# bits.net
KiCad netlist of a schematic drawn in EAGLE
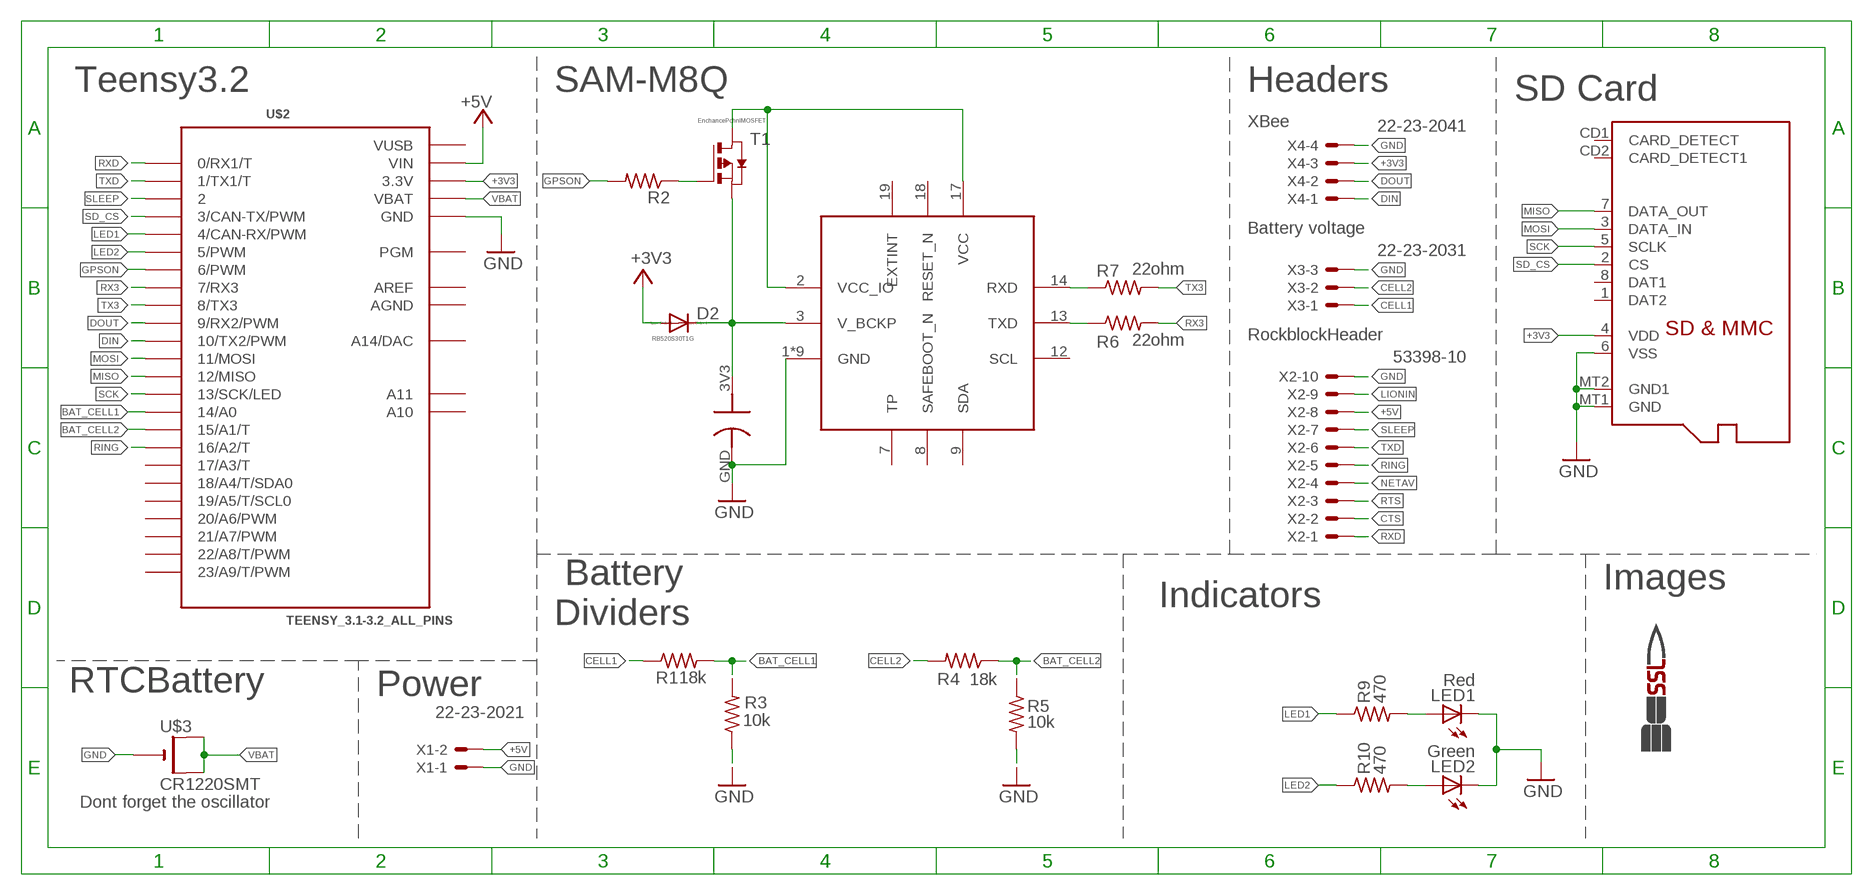
[diagram p0: schematic, sheet 1]

(export (version "E")
  (design (tool "Eeschema 10.0.6"))
  (components
    (comp (ref "C1")
      (value "0.2F elna supercap")
      (footprint "eagle-import:ELNASUPERCAP")
      (libsource (lib "eagle-import") (part "DCK-3RE204T614-ES"))
    )
    (comp (ref "D2")
      (value "RB520S30T1G")
      (footprint "eagle-import:SOD523")
      (libsource (lib "eagle-import") (part "DIODE-SOD523"))
    )
    (comp (ref "IC1")
      (value "SAM-M8Q")
      (footprint "eagle-import:SAM-M8Q")
      (libsource (lib "eagle-import") (part "SAM-M8Q"))
    )
    (comp (ref "IMAG1")
      (value "SSL.3IN_SILK")
      (footprint "eagle-import:SSL_SILK_.3IN")
      (libsource (lib "eagle-import") (part "SSL.3IN_SILK"))
    )
    (comp (ref "LED1")
      (value "Red")
      (footprint "eagle-import:CHIP-LED0603")
      (libsource (lib "eagle-import") (part "LEDCHIP-LED0603"))
    )
    (comp (ref "LED2")
      (value "Green")
      (footprint "eagle-import:CHIP-LED0603")
      (libsource (lib "eagle-import") (part "LEDCHIP-LED0603"))
    )
    (comp (ref "R1")
      (value "18k")
      (footprint "eagle-import:R0603")
      (libsource (lib "eagle-import") (part "R-US_R0603"))
    )
    (comp (ref "R2")
      (value "R-US_R0603")
      (footprint "eagle-import:R0603")
      (libsource (lib "eagle-import") (part "R-US_R0603"))
    )
    (comp (ref "R3")
      (value "10k")
      (footprint "eagle-import:R0603")
      (libsource (lib "eagle-import") (part "R-US_R0603"))
    )
    (comp (ref "R4")
      (value "18k")
      (footprint "eagle-import:R0603")
      (libsource (lib "eagle-import") (part "R-US_R0603"))
    )
    (comp (ref "R5")
      (value "10k")
      (footprint "eagle-import:R0603")
      (libsource (lib "eagle-import") (part "R-US_R0603"))
    )
    (comp (ref "R6")
      (value "22ohm")
      (footprint "eagle-import:R0603")
      (libsource (lib "eagle-import") (part "R-US_R0603"))
    )
    (comp (ref "R7")
      (value "22ohm")
      (footprint "eagle-import:R0603")
      (libsource (lib "eagle-import") (part "R-US_R0603"))
    )
    (comp (ref "R9")
      (value "470")
      (footprint "eagle-import:R0603")
      (libsource (lib "eagle-import") (part "R-US_R0603"))
    )
    (comp (ref "R10")
      (value "470")
      (footprint "eagle-import:R0603")
      (libsource (lib "eagle-import") (part "R-US_R0603"))
    )
    (comp (ref "T1")
      (value "EnchancePchnlMOSFET")
      (footprint "eagle-import:SOT-23")
      (libsource (lib "eagle-import") (part "PMOSSOT23"))
    )
    (comp (ref "U$1")
      (value "MICROSD")
      (footprint "eagle-import:MICROSD")
      (libsource (lib "eagle-import") (part "MICROSD"))
    )
    (comp (ref "U$2")
      (value "TEENSY_3.1-3.2_ALL_PINS")
      (footprint "eagle-import:TEENSY_3.0-3.2&LC_ALL_PINS")
      (libsource (lib "eagle-import") (part "TEENSY_3.1-3.2_ALL_PINS"))
    )
    (comp (ref "U$3")
      (value "CR1220SMT")
      (footprint "eagle-import:CR1220-SMD")
      (libsource (lib "eagle-import") (part "CR1220SMT"))
    )
    (comp (ref "X1")
      (value "22-23-2021")
      (footprint "eagle-import:22-23-2021")
      (fields (field (name "MF") "MOLEX"))
      (libsource (lib "eagle-import") (part "22-23-2021"))
    )
    (comp (ref "X2")
      (value "53398-10")
      (footprint "eagle-import:53398-10")
      (fields (field (name "MF") "MOLEX") (field (name "MPN") "53398-1071"))
      (libsource (lib "eagle-import") (part "53?-10398"))
    )
    (comp (ref "X3")
      (value "22-23-2031")
      (footprint "eagle-import:22-23-2031")
      (fields (field (name "MF") "MOLEX"))
      (libsource (lib "eagle-import") (part "22-23-2031"))
    )
    (comp (ref "X4")
      (value "22-23-2041")
      (footprint "eagle-import:22-23-2041")
      (fields (field (name "MF") "MOLEX"))
      (libsource (lib "eagle-import") (part "22-23-2041"))
    )
  )
  (nets
    (net (code "1") (name "+3V3") (class "Default")
      (node (ref "D2") (pin "A") (pinfunction "A_A") (pintype "passive"))
      (node (ref "U$1") (pin "4") (pinfunction "VDD_4") (pintype "power_in"))
      (node (ref "U$2") (pin "3.3V") (pinfunction "3.3V_3.3V") (pintype "power_in"))
      (node (ref "U$2") (pin "3.3V1") (pinfunction "3.3V_3.3V1") (pintype "power_in"))
      (node (ref "X4") (pin "3") (pinfunction "S_3") (pintype "passive"))
    )
    (net (code "2") (name "+5V") (class "Default")
      (node (ref "U$2") (pin "VIN") (pinfunction "VIN_VIN") (pintype "power_in"))
      (node (ref "X1") (pin "2") (pinfunction "S_2") (pintype "passive"))
      (node (ref "X2") (pin "8") (pinfunction "S_8") (pintype "passive"))
    )
    (net (code "3") (name "/AGND") (class "Default")
      (node (ref "U$2") (pin "AGND") (pinfunction "AGND_AGND") (pintype "power_in"))
    )
    (net (code "4") (name "/AREF") (class "Default")
      (node (ref "U$2") (pin "AREF") (pinfunction "AREF_AREF") (pintype "power_in"))
    )
    (net (code "5") (name "/VUSB") (class "Default")
      (node (ref "U$2") (pin "VUSB") (pinfunction "VUSB_VUSB") (pintype "power_in"))
    )
    (net (code "6") (name "BAT_CELL1") (class "Default")
      (node (ref "R1") (pin "2") (pinfunction "2_2") (pintype "passive"))
      (node (ref "R3") (pin "2") (pinfunction "2_2") (pintype "passive"))
      (node (ref "U$2") (pin "14/A0") (pinfunction "14/A0_14/A0") (pintype "bidirectional"))
    )
    (net (code "7") (name "BAT_CELL2") (class "Default")
      (node (ref "R4") (pin "1") (pinfunction "1_1") (pintype "passive"))
      (node (ref "R5") (pin "1") (pinfunction "1_1") (pintype "passive"))
      (node (ref "U$2") (pin "15/A1") (pinfunction "15/A1/T_15/A1") (pintype "bidirectional"))
    )
    (net (code "8") (name "CELL1") (class "Default")
      (node (ref "R1") (pin "1") (pinfunction "1_1") (pintype "passive"))
      (node (ref "X3") (pin "1") (pinfunction "S_1") (pintype "passive"))
    )
    (net (code "9") (name "CELL2") (class "Default")
      (node (ref "R4") (pin "2") (pinfunction "2_2") (pintype "passive"))
      (node (ref "X3") (pin "2") (pinfunction "S_2") (pintype "passive"))
    )
    (net (code "10") (name "CTS") (class "Default")
      (node (ref "X2") (pin "2") (pinfunction "S_2") (pintype "passive"))
    )
    (net (code "11") (name "DIN") (class "Default")
      (node (ref "U$2") (pin "10") (pinfunction "10/TX2/PWM_10") (pintype "bidirectional"))
      (node (ref "X4") (pin "1") (pinfunction "S_1") (pintype "passive"))
    )
    (net (code "12") (name "DOUT") (class "Default")
      (node (ref "U$2") (pin "9") (pinfunction "9/RX2/PWM_9") (pintype "bidirectional"))
      (node (ref "X4") (pin "2") (pinfunction "S_2") (pintype "passive"))
    )
    (net (code "13") (name "GND") (class "Default")
      (node (ref "C1") (pin "GND") (pinfunction "GND_GND") (pintype "bidirectional"))
      (node (ref "IC1") (pin "1") (pinfunction "GND_1") (pintype "bidirectional"))
      (node (ref "IC1") (pin "10") (pinfunction "GND_10") (pintype "bidirectional"))
      (node (ref "IC1") (pin "11") (pinfunction "GND_11") (pintype "bidirectional"))
      (node (ref "IC1") (pin "15") (pinfunction "GND_15") (pintype "bidirectional"))
      (node (ref "IC1") (pin "16") (pinfunction "GND_16") (pintype "bidirectional"))
      (node (ref "IC1") (pin "20") (pinfunction "GND_20") (pintype "bidirectional"))
      (node (ref "IC1") (pin "4") (pinfunction "GND_4") (pintype "bidirectional"))
      (node (ref "IC1") (pin "5") (pinfunction "GND_5") (pintype "bidirectional"))
      (node (ref "IC1") (pin "6") (pinfunction "GND_6") (pintype "bidirectional"))
      (node (ref "LED1") (pin "C") (pinfunction "C_C") (pintype "passive"))
      (node (ref "LED2") (pin "C") (pinfunction "C_C") (pintype "passive"))
      (node (ref "R3") (pin "1") (pinfunction "1_1") (pintype "passive"))
      (node (ref "R5") (pin "2") (pinfunction "2_2") (pintype "passive"))
      (node (ref "U$1") (pin "6") (pinfunction "VSS_6") (pintype "power_in"))
      (node (ref "U$1") (pin "MT1") (pinfunction "GND_MT1") (pintype "power_in"))
      (node (ref "U$1") (pin "MT2") (pinfunction "GND1_MT2") (pintype "power_in"))
      (node (ref "U$2") (pin "GND") (pinfunction "GND_GND") (pintype "power_in"))
      (node (ref "U$2") (pin "GND1") (pinfunction "GND_GND1") (pintype "power_in"))
      (node (ref "U$3") (pin "-") (pinfunction "-_-") (pintype "passive"))
      (node (ref "X1") (pin "1") (pinfunction "S_1") (pintype "passive"))
      (node (ref "X2") (pin "10") (pinfunction "S_10") (pintype "passive"))
      (node (ref "X3") (pin "3") (pinfunction "S_3") (pintype "passive"))
      (node (ref "X4") (pin "4") (pinfunction "S_4") (pintype "passive"))
    )
    (net (code "14") (name "GPSON") (class "Default")
      (node (ref "R2") (pin "2") (pinfunction "2_2") (pintype "passive"))
      (node (ref "U$2") (pin "6") (pinfunction "6/PWM_6") (pintype "bidirectional"))
    )
    (net (code "15") (name "LED1") (class "Default")
      (node (ref "R9") (pin "1") (pinfunction "1_1") (pintype "passive"))
      (node (ref "U$2") (pin "4") (pinfunction "4/CAN-RX/PWM_4") (pintype "bidirectional"))
    )
    (net (code "16") (name "LED2") (class "Default")
      (node (ref "R10") (pin "1") (pinfunction "1_1") (pintype "passive"))
      (node (ref "U$2") (pin "5") (pinfunction "5/PWM_5") (pintype "bidirectional"))
    )
    (net (code "17") (name "LIONIN") (class "Default")
      (node (ref "X2") (pin "9") (pinfunction "S_9") (pintype "passive"))
    )
    (net (code "18") (name "MISO") (class "Default")
      (node (ref "U$1") (pin "7") (pinfunction "DATA_OUT_7") (pintype "output"))
      (node (ref "U$2") (pin "12") (pinfunction "12/MISO_12") (pintype "bidirectional"))
    )
    (net (code "19") (name "MOSI") (class "Default")
      (node (ref "U$1") (pin "3") (pinfunction "DATA_IN_3") (pintype "input"))
      (node (ref "U$2") (pin "11") (pinfunction "11/MOSI_11") (pintype "bidirectional"))
    )
    (net (code "20") (name "NETAV") (class "Default")
      (node (ref "X2") (pin "4") (pinfunction "S_4") (pintype "passive"))
    )
    (net (code "21") (name "Net-(IC1-RXD)") (class "Default")
      (node (ref "IC1") (pin "14") (pinfunction "RXD_14") (pintype "bidirectional"))
      (node (ref "R7") (pin "1") (pinfunction "1_1") (pintype "passive"))
    )
    (net (code "22") (name "Net-(IC1-TXD)") (class "Default")
      (node (ref "IC1") (pin "13") (pinfunction "TXD_13") (pintype "bidirectional"))
      (node (ref "R6") (pin "1") (pinfunction "1_1") (pintype "passive"))
    )
    (net (code "23") (name "Net-(IC1-VCC)") (class "Default")
      (node (ref "IC1") (pin "17") (pinfunction "VCC_17") (pintype "bidirectional"))
      (node (ref "IC1") (pin "2") (pinfunction "VCC_IO_2") (pintype "bidirectional"))
      (node (ref "T1") (pin "1") (pinfunction "D_1") (pintype "passive"))
    )
    (net (code "24") (name "Net-(IC1-V_BCKP)") (class "Default")
      (node (ref "C1") (pin "3V3") (pinfunction "3V3_3V3") (pintype "bidirectional"))
      (node (ref "D2") (pin "C") (pinfunction "C_C") (pintype "passive"))
      (node (ref "IC1") (pin "3") (pinfunction "V_BCKP_3") (pintype "bidirectional"))
      (node (ref "T1") (pin "2") (pinfunction "S_2") (pintype "passive"))
    )
    (net (code "25") (name "Net-(LED1-PadA)") (class "Default")
      (node (ref "LED1") (pin "A") (pinfunction "A_A") (pintype "passive"))
      (node (ref "R9") (pin "2") (pinfunction "2_2") (pintype "passive"))
    )
    (net (code "26") (name "Net-(LED2-PadA)") (class "Default")
      (node (ref "LED2") (pin "A") (pinfunction "A_A") (pintype "passive"))
      (node (ref "R10") (pin "2") (pinfunction "2_2") (pintype "passive"))
    )
    (net (code "27") (name "Net-(T1-G)") (class "Default")
      (node (ref "R2") (pin "1") (pinfunction "1_1") (pintype "passive"))
      (node (ref "T1") (pin "3") (pinfunction "G_3") (pintype "passive"))
    )
    (net (code "28") (name "RING") (class "Default")
      (node (ref "U$2") (pin "16/A2") (pinfunction "16/A2/T_16/A2") (pintype "bidirectional"))
      (node (ref "X2") (pin "5") (pinfunction "S_5") (pintype "passive"))
    )
    (net (code "29") (name "RTS") (class "Default")
      (node (ref "X2") (pin "3") (pinfunction "S_3") (pintype "passive"))
    )
    (net (code "30") (name "RX3") (class "Default")
      (node (ref "R6") (pin "2") (pinfunction "2_2") (pintype "passive"))
      (node (ref "U$2") (pin "7") (pinfunction "7/RX3_7") (pintype "bidirectional"))
    )
    (net (code "31") (name "RXD") (class "Default")
      (node (ref "U$2") (pin "0") (pinfunction "0/RX1/T_0") (pintype "bidirectional"))
      (node (ref "X2") (pin "1") (pinfunction "S_1") (pintype "passive"))
    )
    (net (code "32") (name "SCK") (class "Default")
      (node (ref "U$1") (pin "5") (pinfunction "SCLK_5") (pintype "input"))
      (node (ref "U$2") (pin "13") (pinfunction "13/SCK/LED_13") (pintype "bidirectional"))
    )
    (net (code "33") (name "SD_CS") (class "Default")
      (node (ref "U$1") (pin "2") (pinfunction "CS_2") (pintype "input"))
      (node (ref "U$2") (pin "3") (pinfunction "3/CAN-TX/PWM_3") (pintype "bidirectional"))
    )
    (net (code "34") (name "SLEEP") (class "Default")
      (node (ref "U$2") (pin "2") (pinfunction "2_2") (pintype "bidirectional"))
      (node (ref "X2") (pin "7") (pinfunction "S_7") (pintype "passive"))
    )
    (net (code "35") (name "TX3") (class "Default")
      (node (ref "R7") (pin "2") (pinfunction "2_2") (pintype "passive"))
      (node (ref "U$2") (pin "8") (pinfunction "8/TX3_8") (pintype "bidirectional"))
    )
    (net (code "36") (name "TXD") (class "Default")
      (node (ref "U$2") (pin "1") (pinfunction "1/TX1/T_1") (pintype "bidirectional"))
      (node (ref "X2") (pin "6") (pinfunction "S_6") (pintype "passive"))
    )
    (net (code "37") (name "VBAT") (class "Default")
      (node (ref "U$2") (pin "VBAT") (pinfunction "VBAT_VBAT") (pintype "power_in"))
      (node (ref "U$3") (pin "+$1") (pinfunction "+_+$1") (pintype "passive"))
      (node (ref "U$3") (pin "+$2") (pinfunction "+1_+$2") (pintype "passive"))
    )
    (net (code "38") (name "unconnected-(IC1-EXTINT-Pad19)") (class "Default")
      (node (ref "IC1") (pin "19") (pinfunction "EXTINT_19") (pintype "bidirectional"))
    )
    (net (code "39") (name "unconnected-(IC1-RESET_N-Pad18)") (class "Default")
      (node (ref "IC1") (pin "18") (pinfunction "RESET_N_18") (pintype "bidirectional"))
    )
    (net (code "40") (name "unconnected-(IC1-SAFEBOOT_N-Pad8)") (class "Default")
      (node (ref "IC1") (pin "8") (pinfunction "SAFEBOOT_N_8") (pintype "bidirectional"))
    )
    (net (code "41") (name "unconnected-(IC1-SCL-Pad12)") (class "Default")
      (node (ref "IC1") (pin "12") (pinfunction "SCL_12") (pintype "bidirectional"))
    )
    (net (code "42") (name "unconnected-(IC1-SDA-Pad9)") (class "Default")
      (node (ref "IC1") (pin "9") (pinfunction "SDA_9") (pintype "bidirectional"))
    )
    (net (code "43") (name "unconnected-(IC1-TP-Pad7)") (class "Default")
      (node (ref "IC1") (pin "7") (pinfunction "TP_7") (pintype "bidirectional"))
    )
    (net (code "44") (name "unconnected-(U$1-CARD_DETECT-PadCD1)") (class "Default")
      (node (ref "U$1") (pin "CD1") (pinfunction "CARD_DETECT_CD1") (pintype "passive"))
    )
    (net (code "45") (name "unconnected-(U$1-CARD_DETECT1-PadCD2)") (class "Default")
      (node (ref "U$1") (pin "CD2") (pinfunction "CARD_DETECT1_CD2") (pintype "passive"))
    )
    (net (code "46") (name "unconnected-(U$1-DAT1-Pad8)") (class "Default")
      (node (ref "U$1") (pin "8") (pinfunction "DAT1_8") (pintype "bidirectional"))
    )
    (net (code "47") (name "unconnected-(U$1-DAT2-Pad1)") (class "Default")
      (node (ref "U$1") (pin "1") (pinfunction "DAT2_1") (pintype "bidirectional"))
    )
    (net (code "48") (name "unconnected-(U$2-17{slash}A3{slash}T-Pad17{slash}A3)") (class "Default")
      (node (ref "U$2") (pin "17/A3") (pinfunction "17/A3/T_17/A3") (pintype "bidirectional"))
    )
    (net (code "49") (name "unconnected-(U$2-18{slash}A4{slash}T{slash}SDA0-Pad18{slash}A4)") (class "Default")
      (node (ref "U$2") (pin "18/A4") (pinfunction "18/A4/T/SDA0_18/A4") (pintype "bidirectional"))
    )
    (net (code "50") (name "unconnected-(U$2-19{slash}A5{slash}T{slash}SCL0-Pad19{slash}A5)") (class "Default")
      (node (ref "U$2") (pin "19/A5") (pinfunction "19/A5/T/SCL0_19/A5") (pintype "bidirectional"))
    )
    (net (code "51") (name "unconnected-(U$2-20{slash}A6{slash}PWM-Pad20{slash}A6)") (class "Default")
      (node (ref "U$2") (pin "20/A6") (pinfunction "20/A6/PWM_20/A6") (pintype "bidirectional"))
    )
    (net (code "52") (name "unconnected-(U$2-21{slash}A7{slash}PWM-Pad21{slash}A7)") (class "Default")
      (node (ref "U$2") (pin "21/A7") (pinfunction "21/A7/PWM_21/A7") (pintype "bidirectional"))
    )
    (net (code "53") (name "unconnected-(U$2-22{slash}A8{slash}T{slash}PWM-Pad22{slash}A8)") (class "Default")
      (node (ref "U$2") (pin "22/A8") (pinfunction "22/A8/T/PWM_22/A8") (pintype "bidirectional"))
    )
    (net (code "54") (name "unconnected-(U$2-23{slash}A9{slash}T{slash}PWM-Pad23{slash}A9)") (class "Default")
      (node (ref "U$2") (pin "23/A9") (pinfunction "23/A9/T/PWM_23/A9") (pintype "bidirectional"))
    )
    (net (code "55") (name "unconnected-(U$2-A14{slash}DAC-PadRESET{slash}DAC)") (class "Default")
      (node (ref "U$2") (pin "RESET/DAC") (pinfunction "A14/DAC_RESET/DAC") (pintype "bidirectional"))
    )
    (net (code "56") (name "unconnected-(U$2-PadA10)") (class "Default")
      (node (ref "U$2") (pin "A10") (pinfunction "A10_A10") (pintype "bidirectional"))
    )
    (net (code "57") (name "unconnected-(U$2-PadA11)") (class "Default")
      (node (ref "U$2") (pin "A11") (pinfunction "A11_A11") (pintype "bidirectional"))
    )
    (net (code "58") (name "unconnected-(U$2-PadPGM)") (class "Default")
      (node (ref "U$2") (pin "PGM") (pinfunction "PGM_PGM") (pintype "bidirectional"))
    )
  )
)
